# PuenteH.net
KiCad netlist of a schematic drawn in EAGLE
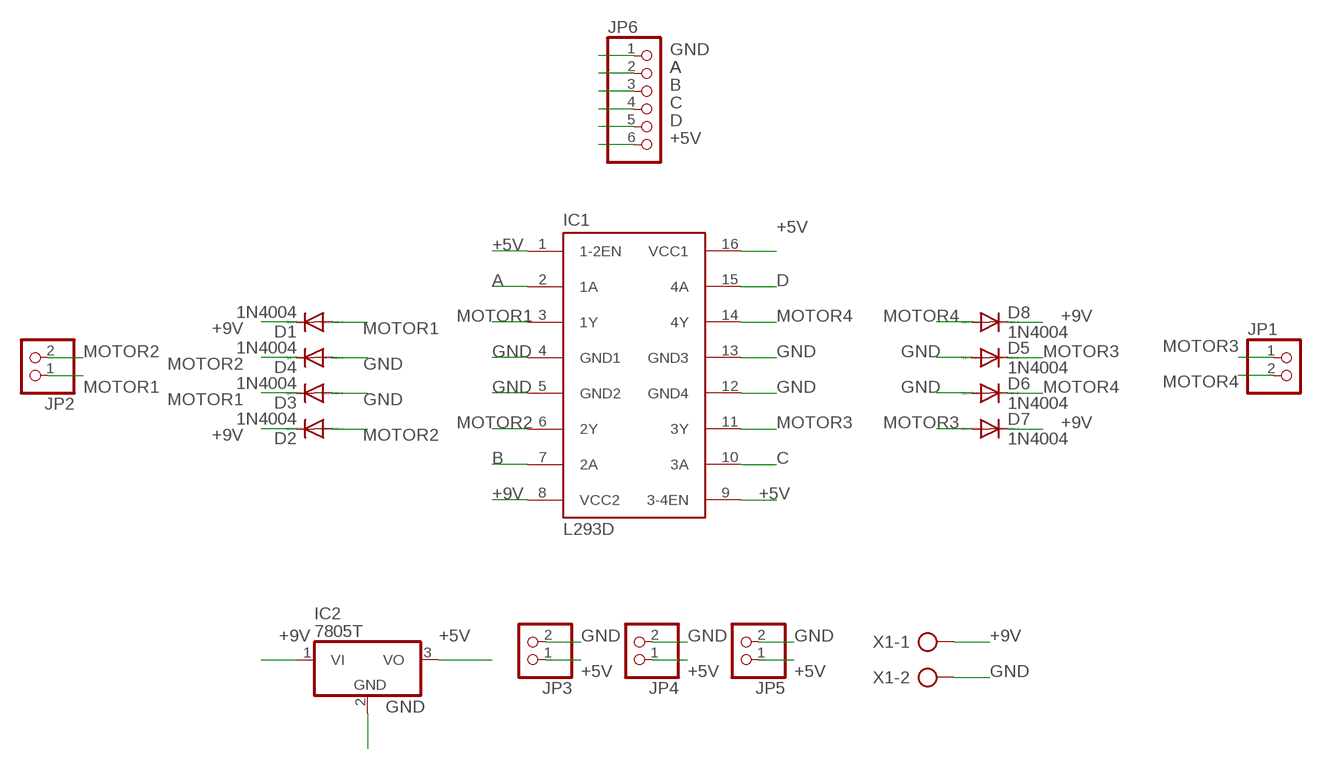
[diagram p0: schematic, sheet 1]

(export (version "E")
  (design (tool "Eeschema 10.0.6"))
  (components
    (comp (ref "D1")
      (value "1N4004")
      (footprint "eagle-import:DO41-10")
      (libsource (lib "eagle-import") (part "1N4004"))
    )
    (comp (ref "D2")
      (value "1N4004")
      (footprint "eagle-import:DO41-10")
      (libsource (lib "eagle-import") (part "1N4004"))
    )
    (comp (ref "D3")
      (value "1N4004")
      (footprint "eagle-import:DO41-10")
      (libsource (lib "eagle-import") (part "1N4004"))
    )
    (comp (ref "D4")
      (value "1N4004")
      (footprint "eagle-import:DO41-10")
      (libsource (lib "eagle-import") (part "1N4004"))
    )
    (comp (ref "D5")
      (value "1N4004")
      (footprint "eagle-import:DO41-10")
      (libsource (lib "eagle-import") (part "1N4004"))
    )
    (comp (ref "D6")
      (value "1N4004")
      (footprint "eagle-import:DO41-10")
      (libsource (lib "eagle-import") (part "1N4004"))
    )
    (comp (ref "D7")
      (value "1N4004")
      (footprint "eagle-import:DO41-10")
      (libsource (lib "eagle-import") (part "1N4004"))
    )
    (comp (ref "D8")
      (value "1N4004")
      (footprint "eagle-import:DO41-10")
      (libsource (lib "eagle-import") (part "1N4004"))
    )
    (comp (ref "IC1")
      (value "L293D")
      (footprint "eagle-import:DIL16")
      (libsource (lib "eagle-import") (part "L293D"))
    )
    (comp (ref "IC2")
      (value "7805T")
      (footprint "eagle-import:TO220H")
      (libsource (lib "eagle-import") (part "78T05"))
    )
    (comp (ref "JP1")
      (value "PINHD-1X2")
      (footprint "eagle-import:1X02")
      (libsource (lib "eagle-import") (part "PINHD-1X2"))
    )
    (comp (ref "JP2")
      (value "PINHD-1X2")
      (footprint "eagle-import:1X02")
      (libsource (lib "eagle-import") (part "PINHD-1X2"))
    )
    (comp (ref "JP3")
      (value "PINHD-1X2")
      (footprint "eagle-import:1X02")
      (libsource (lib "eagle-import") (part "PINHD-1X2"))
    )
    (comp (ref "JP4")
      (value "PINHD-1X2")
      (footprint "eagle-import:1X02")
      (libsource (lib "eagle-import") (part "PINHD-1X2"))
    )
    (comp (ref "JP5")
      (value "PINHD-1X2")
      (footprint "eagle-import:1X02")
      (libsource (lib "eagle-import") (part "PINHD-1X2"))
    )
    (comp (ref "JP6")
      (value "PINHD-1X6")
      (footprint "eagle-import:1X06")
      (libsource (lib "eagle-import") (part "PINHD-1X6"))
    )
    (comp (ref "X1")
      (value "AK500/2-H")
      (footprint "eagle-import:AK500_2-H")
      (libsource (lib "eagle-import") (part "AK500/2-H"))
    )
  )
  (nets
    (net (code "1") (name "/+5V") (class "Default")
      (node (ref "IC1") (pin "1") (pinfunction "1-2EN_1") (pintype "input"))
      (node (ref "IC1") (pin "16") (pinfunction "VCC1_16") (pintype "power_in"))
      (node (ref "IC1") (pin "9") (pinfunction "3-4EN_9") (pintype "input"))
      (node (ref "IC2") (pin "3") (pinfunction "VO_3") (pintype "passive"))
      (node (ref "JP3") (pin "1") (pinfunction "1_1") (pintype "passive"))
      (node (ref "JP4") (pin "1") (pinfunction "1_1") (pintype "passive"))
      (node (ref "JP5") (pin "1") (pinfunction "1_1") (pintype "passive"))
      (node (ref "JP6") (pin "6") (pinfunction "6_6") (pintype "passive"))
    )
    (net (code "2") (name "/+9V") (class "Default")
      (node (ref "D1") (pin "C") (pinfunction "C_C") (pintype "passive"))
      (node (ref "D2") (pin "C") (pinfunction "C_C") (pintype "passive"))
      (node (ref "D7") (pin "C") (pinfunction "C_C") (pintype "passive"))
      (node (ref "D8") (pin "C") (pinfunction "C_C") (pintype "passive"))
      (node (ref "IC1") (pin "8") (pinfunction "VCC2_8") (pintype "power_in"))
      (node (ref "IC2") (pin "1") (pinfunction "VI_1") (pintype "input"))
      (node (ref "X1") (pin "1") (pinfunction "KL_1") (pintype "passive"))
    )
    (net (code "3") (name "/A") (class "Default")
      (node (ref "IC1") (pin "2") (pinfunction "1A_2") (pintype "input"))
      (node (ref "JP6") (pin "2") (pinfunction "2_2") (pintype "passive"))
    )
    (net (code "4") (name "/B") (class "Default")
      (node (ref "IC1") (pin "7") (pinfunction "2A_7") (pintype "input"))
      (node (ref "JP6") (pin "3") (pinfunction "3_3") (pintype "passive"))
    )
    (net (code "5") (name "/C") (class "Default")
      (node (ref "IC1") (pin "10") (pinfunction "3A_10") (pintype "input"))
      (node (ref "JP6") (pin "4") (pinfunction "4_4") (pintype "passive"))
    )
    (net (code "6") (name "/D") (class "Default")
      (node (ref "IC1") (pin "15") (pinfunction "4A_15") (pintype "input"))
      (node (ref "JP6") (pin "5") (pinfunction "5_5") (pintype "passive"))
    )
    (net (code "7") (name "/GND") (class "Default")
      (node (ref "D3") (pin "A") (pinfunction "A_A") (pintype "passive"))
      (node (ref "D4") (pin "A") (pinfunction "A_A") (pintype "passive"))
      (node (ref "D5") (pin "A") (pinfunction "A_A") (pintype "passive"))
      (node (ref "D6") (pin "A") (pinfunction "A_A") (pintype "passive"))
      (node (ref "IC1") (pin "12") (pinfunction "GND4_12") (pintype "power_in"))
      (node (ref "IC1") (pin "13") (pinfunction "GND3_13") (pintype "power_in"))
      (node (ref "IC1") (pin "4") (pinfunction "GND1_4") (pintype "power_in"))
      (node (ref "IC1") (pin "5") (pinfunction "GND2_5") (pintype "power_in"))
      (node (ref "IC2") (pin "2") (pinfunction "GND_2") (pintype "passive"))
      (node (ref "JP3") (pin "2") (pinfunction "2_2") (pintype "passive"))
      (node (ref "JP4") (pin "2") (pinfunction "2_2") (pintype "passive"))
      (node (ref "JP5") (pin "2") (pinfunction "2_2") (pintype "passive"))
      (node (ref "JP6") (pin "1") (pinfunction "1_1") (pintype "passive"))
      (node (ref "X1") (pin "2") (pinfunction "KL_2") (pintype "passive"))
    )
    (net (code "8") (name "/MOTOR1") (class "Default")
      (node (ref "D1") (pin "A") (pinfunction "A_A") (pintype "passive"))
      (node (ref "D3") (pin "C") (pinfunction "C_C") (pintype "passive"))
      (node (ref "IC1") (pin "3") (pinfunction "1Y_3") (pintype "output"))
      (node (ref "JP2") (pin "1") (pinfunction "1_1") (pintype "passive"))
    )
    (net (code "9") (name "/MOTOR2") (class "Default")
      (node (ref "D2") (pin "A") (pinfunction "A_A") (pintype "passive"))
      (node (ref "D4") (pin "C") (pinfunction "C_C") (pintype "passive"))
      (node (ref "IC1") (pin "6") (pinfunction "2Y_6") (pintype "output"))
      (node (ref "JP2") (pin "2") (pinfunction "2_2") (pintype "passive"))
    )
    (net (code "10") (name "/MOTOR3") (class "Default")
      (node (ref "D5") (pin "C") (pinfunction "C_C") (pintype "passive"))
      (node (ref "D7") (pin "A") (pinfunction "A_A") (pintype "passive"))
      (node (ref "IC1") (pin "11") (pinfunction "3Y_11") (pintype "output"))
      (node (ref "JP1") (pin "1") (pinfunction "1_1") (pintype "passive"))
    )
    (net (code "11") (name "/MOTOR4") (class "Default")
      (node (ref "D6") (pin "C") (pinfunction "C_C") (pintype "passive"))
      (node (ref "D8") (pin "A") (pinfunction "A_A") (pintype "passive"))
      (node (ref "IC1") (pin "14") (pinfunction "4Y_14") (pintype "output"))
      (node (ref "JP1") (pin "2") (pinfunction "2_2") (pintype "passive"))
    )
  )
)
